# 2022-SS-ZT-1.net
KiCad netlist of a schematic drawn in EasyEDA Pro
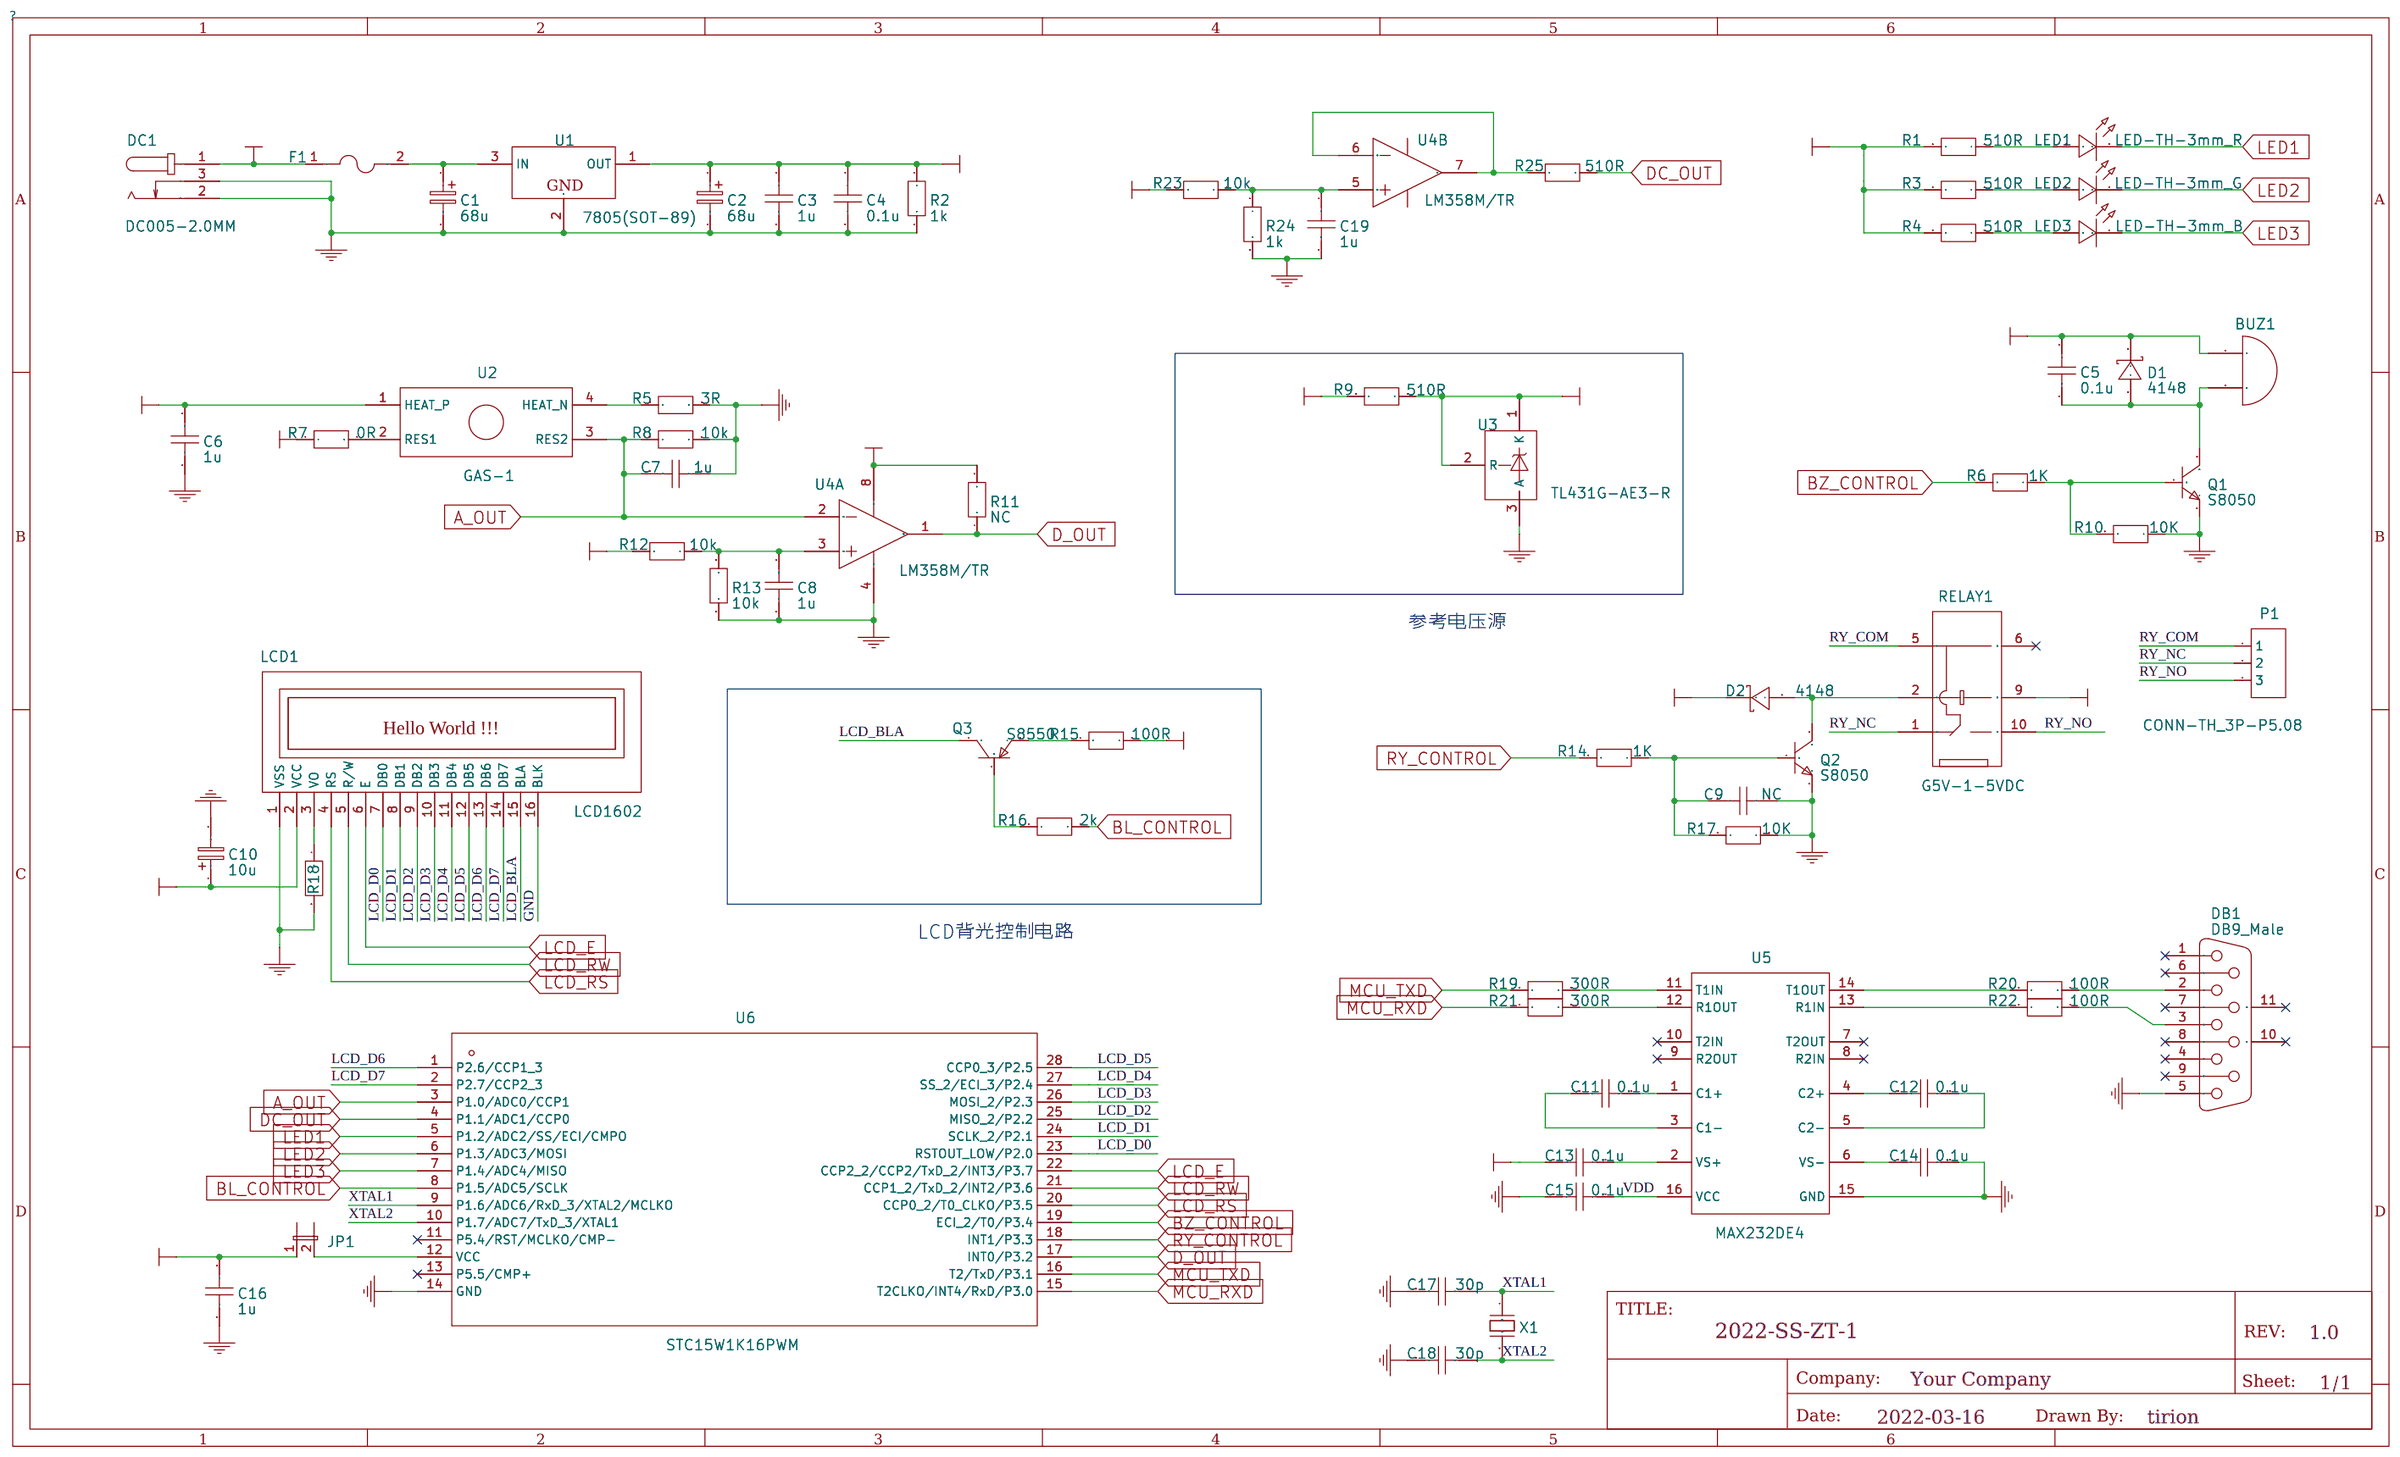
[diagram p0: schematic sheet]

(export (version "E")
  (design (tool "Eeschema 10.0.6"))
  (components
    (comp (ref "BUZ1") (value "BUZ1") (libsource (lib "easyedapro") (part "BUZ1")))
    (comp (ref "C1") (value "68u") (libsource (lib "easyedapro") (part "68u")))
    (comp (ref "C2") (value "68u") (libsource (lib "easyedapro") (part "68u")))
    (comp (ref "C3") (value "1u") (libsource (lib "easyedapro") (part "1u")))
    (comp (ref "C4") (value "0.1u") (libsource (lib "easyedapro") (part "0.1u")))
    (comp (ref "C5") (value "0.1u") (libsource (lib "easyedapro") (part "0.1u")))
    (comp (ref "C6") (value "1u") (libsource (lib "easyedapro") (part "1u")))
    (comp (ref "C7") (value "1u") (libsource (lib "easyedapro") (part "1u")))
    (comp (ref "C8") (value "1u") (libsource (lib "easyedapro") (part "1u")))
    (comp (ref "C9") (value "NC") (libsource (lib "easyedapro") (part "NC")))
    (comp (ref "C10") (value "10u") (libsource (lib "easyedapro") (part "10u")))
    (comp (ref "C11") (value "0.1u") (libsource (lib "easyedapro") (part "0.1u")))
    (comp (ref "C12") (value "0.1u") (libsource (lib "easyedapro") (part "0.1u")))
    (comp (ref "C13") (value "0.1u") (libsource (lib "easyedapro") (part "0.1u")))
    (comp (ref "C14") (value "0.1u") (libsource (lib "easyedapro") (part "0.1u")))
    (comp (ref "C15") (value "0.1u") (libsource (lib "easyedapro") (part "0.1u")))
    (comp (ref "C16") (value "1u") (libsource (lib "easyedapro") (part "1u")))
    (comp (ref "C17") (value "30p") (libsource (lib "easyedapro") (part "30p")))
    (comp (ref "C18") (value "30p") (libsource (lib "easyedapro") (part "30p")))
    (comp (ref "C19") (value "1u") (libsource (lib "easyedapro") (part "1u")))
    (comp (ref "D1")
      (value "4148")
      (fields (field (name "Manufacturer Part") "SS14") (field (name "Manufacturer") "MDD"))
      (libsource (lib "easyedapro") (part "4148"))
    )
    (comp (ref "D2")
      (value "4148")
      (fields (field (name "Manufacturer Part") "SS14") (field (name "Manufacturer") "MDD"))
      (libsource (lib "easyedapro") (part "4148"))
    )
    (comp (ref "DB1")
      (value "DB9_Male")
      (fields (field (name "Manufacturer") "Amphenol"))
      (libsource (lib "easyedapro") (part "DB9_Male"))
    )
    (comp (ref "DC1")
      (value "DC005-2.0MM")
      (fields (field (name "Manufacturer") "SOFNG"))
      (libsource (lib "easyedapro") (part "DC005-2.0MM"))
    )
    (comp (ref "F1") (value "FUSE_F1812_FUSE") (libsource (lib "easyedapro") (part "FUSE_F1812_FUSE")))
    (comp (ref "JP1") (value "JUMPER2") (libsource (lib "easyedapro") (part "JUMPER2")))
    (comp (ref "LCD1")
      (value "LCD1602")
      (fields
        (field (name "Manufacturer Part") "LCM1602K-NSW-BBW")
        (field (name "Manufacturer") "LONTECH(厦门龙特)")
      )
      (libsource (lib "easyedapro") (part "LCD1602"))
    )
    (comp (ref "LED1")
      (value "LED-TH-3mm_R")
      (fields
        (field (name "Manufacturer Part") "204-10SDRD/S530-A3-L")
        (field (name "Manufacturer") "EVERLIGHT(台湾亿光)")
      )
      (libsource (lib "easyedapro") (part "LED-TH-3mm_R"))
    )
    (comp (ref "LED2")
      (value "LED-TH-3mm_G")
      (fields
        (field (name "Manufacturer Part") "204-10SYGD/S530-E3")
        (field (name "Manufacturer") "EVERLIGHT(台湾亿光)")
      )
      (libsource (lib "easyedapro") (part "LED-TH-3mm_G"))
    )
    (comp (ref "LED3")
      (value "LED-TH-3mm_B")
      (fields
        (field (name "Manufacturer Part") "204-10SUBC/S400-A4")
        (field (name "Manufacturer") "EVERLIGHT(台湾亿光)")
      )
      (libsource (lib "easyedapro") (part "LED-TH-3mm_B"))
    )
    (comp (ref "P1") (value "CONN-TH_3P-P5.08") (libsource (lib "easyedapro") (part "CONN-TH_3P-P5.08")))
    (comp (ref "Q1")
      (value "S8050")
      (fields (field (name "Manufacturer") "JSMSEMI"))
      (libsource (lib "easyedapro") (part "S8050"))
    )
    (comp (ref "Q2")
      (value "S8050")
      (fields (field (name "Manufacturer") "JSMSEMI"))
      (libsource (lib "easyedapro") (part "S8050"))
    )
    (comp (ref "Q3")
      (value "S8550")
      (fields
        (field (name "Manufacturer Part") "S8550-H")
        (field (name "Manufacturer") "Yangzhou Yangjie Elec Tech")
      )
      (libsource (lib "easyedapro") (part "S8550"))
    )
    (comp (ref "R1") (value "510R") (libsource (lib "easyedapro") (part "510R")))
    (comp (ref "R2") (value "1k") (libsource (lib "easyedapro") (part "1k")))
    (comp (ref "R3") (value "510R") (libsource (lib "easyedapro") (part "510R")))
    (comp (ref "R4") (value "510R") (libsource (lib "easyedapro") (part "510R")))
    (comp (ref "R5") (value "3R") (libsource (lib "easyedapro") (part "3R")))
    (comp (ref "R6") (value "1K") (libsource (lib "easyedapro") (part "1K")))
    (comp (ref "R7") (value "0R") (libsource (lib "easyedapro") (part "0R")))
    (comp (ref "R8") (value "10k") (libsource (lib "easyedapro") (part "10k")))
    (comp (ref "R9") (value "510R") (libsource (lib "easyedapro") (part "510R")))
    (comp (ref "R10") (value "10K") (libsource (lib "easyedapro") (part "10K")))
    (comp (ref "R11") (value "NC") (libsource (lib "") (part "NC_1")))
    (comp (ref "R12") (value "10k") (libsource (lib "easyedapro") (part "10k")))
    (comp (ref "R13") (value "10k") (libsource (lib "easyedapro") (part "10k")))
    (comp (ref "R14") (value "1K") (libsource (lib "easyedapro") (part "1K")))
    (comp (ref "R15") (value "100R") (libsource (lib "easyedapro") (part "100R")))
    (comp (ref "R16") (value "2k") (libsource (lib "easyedapro") (part "2k")))
    (comp (ref "R17") (value "10K") (libsource (lib "easyedapro") (part "10K")))
    (comp (ref "R18") (value "10k") (libsource (lib "easyedapro") (part "10k")))
    (comp (ref "R19") (value "300R") (libsource (lib "easyedapro") (part "300R")))
    (comp (ref "R20") (value "100R") (libsource (lib "easyedapro") (part "100R")))
    (comp (ref "R21") (value "300R") (libsource (lib "easyedapro") (part "300R")))
    (comp (ref "R22") (value "100R") (libsource (lib "easyedapro") (part "100R")))
    (comp (ref "R23") (value "10k") (libsource (lib "easyedapro") (part "10k")))
    (comp (ref "R24") (value "1k") (libsource (lib "easyedapro") (part "1k")))
    (comp (ref "R25") (value "510R") (libsource (lib "easyedapro") (part "510R")))
    (comp (ref "RELAY1")
      (value "G5V-1-5VDC")
      (fields (field (name "Manufacturer") "OMRON"))
      (libsource (lib "easyedapro") (part "G5V-1-5VDC"))
    )
    (comp (ref "U1")
      (value "7805(SOT-89)")
      (fields (field (name "Manufacturer Part") "CJ78L05") (field (name "Manufacturer") "CJ"))
      (libsource (lib "easyedapro") (part "7805(SOT-89)"))
    )
    (comp (ref "U2") (value "GAS-1") (libsource (lib "easyedapro") (part "GAS-1")))
    (comp (ref "U3")
      (value "TL431G-AE3-R")
      (fields (field (name "Manufacturer") "UTC"))
      (libsource (lib "easyedapro") (part "TL431G-AE3-R"))
    )
    (comp (ref "U4")
      (value "LM358M/TR")
      (fields (field (name "Manufacturer") "HGSEMI"))
      (libsource (lib "easyedapro") (part "LM358M/TR"))
    )
    (comp (ref "U5") (value "MAX232DE4") (libsource (lib "easyedapro") (part "MAX232DE4")))
    (comp (ref "U6")
      (value "STC15W1K16PWM")
      (fields (field (name "Manufacturer") "STC"))
      (libsource (lib "easyedapro") (part "STC15W1K16PWM"))
    )
    (comp (ref "X1")
      (value "12MHZ")
      (fields (field (name "Manufacturer Part") "X49UD12MSD2SC") (field (name "Manufacturer") "LCSC"))
      (libsource (lib "easyedapro") (part "12MHZ"))
    )
  )
  (nets
    (net (code "1") (name "/LCD_BLA") (class "Default")
      (node (ref "LCD1") (pin "15") (pinfunction "BLA_15") (pintype "input"))
      (node (ref "Q3") (pin "3") (pinfunction "C_3") (pintype "input"))
    )
    (net (code "2") (name "/LCD_D0") (class "Default")
      (node (ref "LCD1") (pin "7") (pinfunction "DB0_7") (pintype "input"))
      (node (ref "U6") (pin "23") (pinfunction "RSTOUT_LOW/P2.0_23") (pintype "input"))
    )
    (net (code "3") (name "/LCD_D1") (class "Default")
      (node (ref "LCD1") (pin "8") (pinfunction "DB1_8") (pintype "input"))
      (node (ref "U6") (pin "24") (pinfunction "SCLK_2/P2.1_24") (pintype "input"))
    )
    (net (code "4") (name "/LCD_D2") (class "Default")
      (node (ref "LCD1") (pin "9") (pinfunction "DB2_9") (pintype "input"))
      (node (ref "U6") (pin "25") (pinfunction "MISO_2/P2.2_25") (pintype "input"))
    )
    (net (code "5") (name "/LCD_D3") (class "Default")
      (node (ref "LCD1") (pin "10") (pinfunction "DB3_10") (pintype "input"))
      (node (ref "U6") (pin "26") (pinfunction "MOSI_2/P2.3_26") (pintype "input"))
    )
    (net (code "6") (name "/LCD_D4") (class "Default")
      (node (ref "LCD1") (pin "11") (pinfunction "DB4_11") (pintype "input"))
      (node (ref "U6") (pin "27") (pinfunction "SS_2/ECI_3/P2.4_27") (pintype "input"))
    )
    (net (code "7") (name "/LCD_D5") (class "Default")
      (node (ref "LCD1") (pin "12") (pinfunction "DB5_12") (pintype "input"))
      (node (ref "U6") (pin "28") (pinfunction "CCP0_3/P2.5_28") (pintype "input"))
    )
    (net (code "8") (name "/LCD_D6") (class "Default")
      (node (ref "LCD1") (pin "13") (pinfunction "DB6_13") (pintype "input"))
      (node (ref "U6") (pin "1") (pinfunction "P2.6/CCP1_3_1") (pintype "input"))
    )
    (net (code "9") (name "/LCD_D7") (class "Default")
      (node (ref "LCD1") (pin "14") (pinfunction "DB7_14") (pintype "input"))
      (node (ref "U6") (pin "2") (pinfunction "P2.7/CCP2_3_2") (pintype "input"))
    )
    (net (code "10") (name "/RY_COM") (class "Default")
      (node (ref "P1") (pin "1") (pinfunction "1_1") (pintype "input"))
      (node (ref "RELAY1") (pin "5") (pinfunction "5_5") (pintype "input"))
    )
    (net (code "11") (name "/RY_NC") (class "Default")
      (node (ref "P1") (pin "2") (pinfunction "2_2") (pintype "input"))
      (node (ref "RELAY1") (pin "1") (pinfunction "1_1") (pintype "input"))
    )
    (net (code "12") (name "/RY_NO") (class "Default")
      (node (ref "P1") (pin "3") (pinfunction "3_3") (pintype "input"))
      (node (ref "RELAY1") (pin "10") (pinfunction "10_10") (pintype "input"))
    )
    (net (code "13") (name "/XTAL1") (class "Default")
      (node (ref "C17") (pin "1") (pinfunction "1_1") (pintype "input"))
      (node (ref "U6") (pin "9") (pinfunction "P1.6/ADC6/RxD_3/XTAL2/MCLKO_9") (pintype "input"))
      (node (ref "X1") (pin "1") (pinfunction "OSC1_1") (pintype "input"))
    )
    (net (code "14") (name "/XTAL2") (class "Default")
      (node (ref "C18") (pin "1") (pinfunction "1_1") (pintype "input"))
      (node (ref "U6") (pin "10") (pinfunction "P1.7/ADC7/TxD_3/XTAL1_10") (pintype "input"))
      (node (ref "X1") (pin "2") (pinfunction "OSC2_2") (pintype "input"))
    )
    (net (code "15") (name "A_OUT") (class "Default")
      (node (ref "C7") (pin "2") (pinfunction "2_2") (pintype "input"))
      (node (ref "R8") (pin "1") (pinfunction "1_1") (pintype "input"))
      (node (ref "U2") (pin "3") (pinfunction "RES2_3") (pintype "input"))
      (node (ref "U4") (pin "2") (pinfunction "1IN-_2") (pintype "input"))
      (node (ref "U6") (pin "3") (pinfunction "P1.0/ADC0/CCP1_3") (pintype "input"))
    )
    (net (code "16") (name "BL_CONTROL") (class "Default")
      (node (ref "R16") (pin "2") (pinfunction "2_2") (pintype "input"))
      (node (ref "U6") (pin "8") (pinfunction "P1.5/ADC5/SCLK_8") (pintype "input"))
    )
    (net (code "17") (name "BZ_CONTROL") (class "Default")
      (node (ref "R6") (pin "2") (pinfunction "2_2") (pintype "input"))
      (node (ref "U6") (pin "19") (pinfunction "ECI_2/T0/P3.4_19") (pintype "input"))
    )
    (net (code "18") (name "DC_IN") (class "Default")
      (node (ref "DC1") (pin "1") (pinfunction "1_1") (pintype "input"))
      (node (ref "F1") (pin "1") (pinfunction "1_1") (pintype "input"))
      (node (ref "R23") (pin "2") (pinfunction "2_2") (pintype "input"))
    )
    (net (code "19") (name "DC_OUT") (class "Default")
      (node (ref "R25") (pin "1") (pinfunction "1_1") (pintype "input"))
      (node (ref "U6") (pin "4") (pinfunction "P1.1/ADC1/CCP0_4") (pintype "input"))
    )
    (net (code "20") (name "D_OUT") (class "Default")
      (node (ref "R11") (pin "1") (pinfunction "1_1") (pintype "input"))
      (node (ref "U4") (pin "1") (pinfunction "1OUT_1") (pintype "output"))
      (node (ref "U6") (pin "17") (pinfunction "INT0/P3.2_17") (pintype "input"))
    )
    (net (code "21") (name "GND") (class "Default")
      (node (ref "C1") (pin "2") (pinfunction "2_2") (pintype "input"))
      (node (ref "C10") (pin "2") (pinfunction "2_2") (pintype "input"))
      (node (ref "C14") (pin "2") (pinfunction "2_2") (pintype "input"))
      (node (ref "C15") (pin "1") (pinfunction "1_1") (pintype "input"))
      (node (ref "C16") (pin "1") (pinfunction "1_1") (pintype "input"))
      (node (ref "C17") (pin "2") (pinfunction "2_2") (pintype "input"))
      (node (ref "C18") (pin "2") (pinfunction "2_2") (pintype "input"))
      (node (ref "C19") (pin "2") (pinfunction "2_2") (pintype "input"))
      (node (ref "C2") (pin "2") (pinfunction "2_2") (pintype "input"))
      (node (ref "C3") (pin "2") (pinfunction "2_2") (pintype "input"))
      (node (ref "C4") (pin "2") (pinfunction "2_2") (pintype "input"))
      (node (ref "C6") (pin "1") (pinfunction "1_1") (pintype "input"))
      (node (ref "C7") (pin "1") (pinfunction "1_1") (pintype "input"))
      (node (ref "C8") (pin "2") (pinfunction "2_2") (pintype "input"))
      (node (ref "C9") (pin "2") (pinfunction "2_2") (pintype "input"))
      (node (ref "DB1") (pin "5") (pinfunction "5_5") (pintype "input"))
      (node (ref "DC1") (pin "2") (pinfunction "2_2") (pintype "input"))
      (node (ref "DC1") (pin "3") (pinfunction "3_3") (pintype "input"))
      (node (ref "LCD1") (pin "1") (pinfunction "VSS_1") (pintype "input"))
      (node (ref "LCD1") (pin "16") (pinfunction "BLK_16") (pintype "input"))
      (node (ref "Q1") (pin "2") (pinfunction "E_2") (pintype "input"))
      (node (ref "Q2") (pin "2") (pinfunction "E_2") (pintype "input"))
      (node (ref "R10") (pin "1") (pinfunction "1_1") (pintype "input"))
      (node (ref "R13") (pin "2") (pinfunction "2_2") (pintype "input"))
      (node (ref "R17") (pin "1") (pinfunction "1_1") (pintype "input"))
      (node (ref "R18") (pin "2") (pinfunction "2_2") (pintype "input"))
      (node (ref "R2") (pin "2") (pinfunction "2_2") (pintype "input"))
      (node (ref "R24") (pin "2") (pinfunction "2_2") (pintype "input"))
      (node (ref "R5") (pin "2") (pinfunction "2_2") (pintype "input"))
      (node (ref "R8") (pin "2") (pinfunction "2_2") (pintype "input"))
      (node (ref "U1") (pin "2") (pinfunction "GND_2") (pintype "input"))
      (node (ref "U3") (pin "3") (pinfunction "A_3") (pintype "input"))
      (node (ref "U4") (pin "4") (pinfunction "GND_4") (pintype "input"))
      (node (ref "U5") (pin "15") (pinfunction "GND_15") (pintype "input"))
      (node (ref "U6") (pin "14") (pinfunction "GND_14") (pintype "input"))
    )
    (net (code "22") (name "LCD_E") (class "Default")
      (node (ref "LCD1") (pin "6") (pinfunction "E_6") (pintype "input"))
      (node (ref "U6") (pin "22") (pinfunction "CCP2_2/CCP2/TxD_2/INT3/P3.7_22") (pintype "input"))
    )
    (net (code "23") (name "LCD_RS") (class "Default")
      (node (ref "LCD1") (pin "4") (pinfunction "RS_4") (pintype "input"))
      (node (ref "U6") (pin "20") (pinfunction "CCP0_2/T0_CLKO/P3.5_20") (pintype "input"))
    )
    (net (code "24") (name "LCD_RW") (class "Default")
      (node (ref "LCD1") (pin "5") (pinfunction "R/W_5") (pintype "input"))
      (node (ref "U6") (pin "21") (pinfunction "CCP1_2/TxD_2/INT2/P3.6_21") (pintype "input"))
    )
    (net (code "25") (name "LED1") (class "Default")
      (node (ref "LED1") (pin "2") (pinfunction "2_2") (pintype "input"))
      (node (ref "U6") (pin "5") (pinfunction "P1.2/ADC2/SS/ECI/CMPO_5") (pintype "input"))
    )
    (net (code "26") (name "LED2") (class "Default")
      (node (ref "LED2") (pin "2") (pinfunction "2_2") (pintype "input"))
      (node (ref "U6") (pin "6") (pinfunction "P1.3/ADC3/MOSI_6") (pintype "input"))
    )
    (net (code "27") (name "LED3") (class "Default")
      (node (ref "LED3") (pin "2") (pinfunction "2_2") (pintype "input"))
      (node (ref "U6") (pin "7") (pinfunction "P1.4/ADC4/MISO_7") (pintype "input"))
    )
    (net (code "28") (name "MCU_RXD") (class "Default")
      (node (ref "R21") (pin "1") (pinfunction "1_1") (pintype "input"))
      (node (ref "U6") (pin "15") (pinfunction "T2CLKO/INT4/RxD/P3.0_15") (pintype "input"))
    )
    (net (code "29") (name "MCU_TXD") (class "Default")
      (node (ref "R19") (pin "1") (pinfunction "1_1") (pintype "input"))
      (node (ref "U6") (pin "16") (pinfunction "T2/TxD/P3.1_16") (pintype "input"))
    )
    (net (code "30") (name "Net-(BUZ1-B)") (class "Default")
      (node (ref "BUZ1") (pin "2") (pinfunction "B_2") (pintype "input"))
      (node (ref "C5") (pin "1") (pinfunction "1_1") (pintype "input"))
      (node (ref "D1") (pin "2") (pinfunction "A_2") (pintype "input"))
      (node (ref "Q1") (pin "3") (pinfunction "C_3") (pintype "input"))
    )
    (net (code "31") (name "Net-(D2-A)") (class "Default")
      (node (ref "D2") (pin "2") (pinfunction "A_2") (pintype "input"))
      (node (ref "Q2") (pin "3") (pinfunction "C_3") (pintype "input"))
      (node (ref "RELAY1") (pin "2") (pinfunction "2_2") (pintype "input"))
    )
    (net (code "32") (name "Net-(DB1-Pad2)") (class "Default")
      (node (ref "DB1") (pin "2") (pinfunction "2_2") (pintype "input"))
      (node (ref "R20") (pin "2") (pinfunction "2_2") (pintype "input"))
    )
    (net (code "33") (name "Net-(DB1-Pad3)") (class "Default")
      (node (ref "DB1") (pin "3") (pinfunction "3_3") (pintype "input"))
      (node (ref "R22") (pin "2") (pinfunction "2_2") (pintype "input"))
    )
    (net (code "34") (name "Net-(LCD1-VO)") (class "Default")
      (node (ref "LCD1") (pin "3") (pinfunction "VO_3") (pintype "input"))
      (node (ref "R18") (pin "1") (pinfunction "1_1") (pintype "input"))
    )
    (net (code "35") (name "Net-(LED1-Pad1)") (class "Default")
      (node (ref "LED1") (pin "1") (pinfunction "1_1") (pintype "input"))
      (node (ref "R1") (pin "1") (pinfunction "1_1") (pintype "input"))
    )
    (net (code "36") (name "Net-(LED2-Pad1)") (class "Default")
      (node (ref "LED2") (pin "1") (pinfunction "1_1") (pintype "input"))
      (node (ref "R3") (pin "1") (pinfunction "1_1") (pintype "input"))
    )
    (net (code "37") (name "Net-(LED3-Pad1)") (class "Default")
      (node (ref "LED3") (pin "1") (pinfunction "1_1") (pintype "input"))
      (node (ref "R4") (pin "1") (pinfunction "1_1") (pintype "input"))
    )
    (net (code "38") (name "Net-(Q1-B)") (class "Default")
      (node (ref "Q1") (pin "1") (pinfunction "B_1") (pintype "input"))
      (node (ref "R10") (pin "2") (pinfunction "2_2") (pintype "input"))
      (node (ref "R6") (pin "1") (pinfunction "1_1") (pintype "input"))
    )
    (net (code "39") (name "Net-(Q2-B)") (class "Default")
      (node (ref "C9") (pin "1") (pinfunction "1_1") (pintype "input"))
      (node (ref "Q2") (pin "1") (pinfunction "B_1") (pintype "input"))
      (node (ref "R14") (pin "1") (pinfunction "1_1") (pintype "input"))
      (node (ref "R17") (pin "2") (pinfunction "2_2") (pintype "input"))
    )
    (net (code "40") (name "Net-(Q3-B)") (class "Default")
      (node (ref "Q3") (pin "1") (pinfunction "B_1") (pintype "input"))
      (node (ref "R16") (pin "1") (pinfunction "1_1") (pintype "input"))
    )
    (net (code "41") (name "Net-(Q3-E)") (class "Default")
      (node (ref "Q3") (pin "2") (pinfunction "E_2") (pintype "input"))
      (node (ref "R15") (pin "1") (pinfunction "1_1") (pintype "input"))
    )
    (net (code "42") (name "Net-(U1-IN)") (class "Default")
      (node (ref "C1") (pin "1") (pinfunction "1_1") (pintype "input"))
      (node (ref "F1") (pin "2") (pinfunction "2_2") (pintype "input"))
      (node (ref "U1") (pin "3") (pinfunction "IN_3") (pintype "input"))
    )
    (net (code "43") (name "Net-(U2-HEAT_N)") (class "Default")
      (node (ref "R5") (pin "1") (pinfunction "1_1") (pintype "input"))
      (node (ref "U2") (pin "4") (pinfunction "HEAT_N_4") (pintype "input"))
    )
    (net (code "44") (name "Net-(U2-RES1)") (class "Default")
      (node (ref "R7") (pin "2") (pinfunction "2_2") (pintype "input"))
      (node (ref "U2") (pin "2") (pinfunction "RES1_2") (pintype "input"))
    )
    (net (code "45") (name "Net-(U4A-1IN+)") (class "Default")
      (node (ref "C8") (pin "1") (pinfunction "1_1") (pintype "input"))
      (node (ref "R12") (pin "1") (pinfunction "1_1") (pintype "input"))
      (node (ref "R13") (pin "1") (pinfunction "1_1") (pintype "input"))
      (node (ref "U4") (pin "3") (pinfunction "1IN+_3") (pintype "input"))
    )
    (net (code "46") (name "Net-(U4B-2IN+)") (class "Default")
      (node (ref "C19") (pin "1") (pinfunction "1_1") (pintype "input"))
      (node (ref "R23") (pin "1") (pinfunction "1_1") (pintype "input"))
      (node (ref "R24") (pin "1") (pinfunction "1_1") (pintype "input"))
      (node (ref "U4") (pin "5") (pinfunction "2IN+_5") (pintype "input"))
    )
    (net (code "47") (name "Net-(U4B-2IN-)") (class "Default")
      (node (ref "R25") (pin "2") (pinfunction "2_2") (pintype "input"))
      (node (ref "U4") (pin "6") (pinfunction "2IN-_6") (pintype "input"))
      (node (ref "U4") (pin "7") (pinfunction "2OUT_7") (pintype "output"))
    )
    (net (code "48") (name "Net-(U5-C1+)") (class "Default")
      (node (ref "C11") (pin "2") (pinfunction "2_2") (pintype "input"))
      (node (ref "U5") (pin "1") (pinfunction "C1+_1") (pintype "input"))
    )
    (net (code "49") (name "Net-(U5-C1-)") (class "Default")
      (node (ref "C11") (pin "1") (pinfunction "1_1") (pintype "input"))
      (node (ref "U5") (pin "3") (pinfunction "C1-_3") (pintype "input"))
    )
    (net (code "50") (name "Net-(U5-C2+)") (class "Default")
      (node (ref "C12") (pin "1") (pinfunction "1_1") (pintype "input"))
      (node (ref "U5") (pin "4") (pinfunction "C2+_4") (pintype "input"))
    )
    (net (code "51") (name "Net-(U5-C2-)") (class "Default")
      (node (ref "C12") (pin "2") (pinfunction "2_2") (pintype "input"))
      (node (ref "U5") (pin "5") (pinfunction "C2-_5") (pintype "input"))
    )
    (net (code "52") (name "Net-(U5-R1IN)") (class "Default")
      (node (ref "R22") (pin "1") (pinfunction "1_1") (pintype "input"))
      (node (ref "U5") (pin "13") (pinfunction "R1IN_13") (pintype "input"))
    )
    (net (code "53") (name "Net-(U5-R1OUT)") (class "Default")
      (node (ref "R21") (pin "2") (pinfunction "2_2") (pintype "input"))
      (node (ref "U5") (pin "12") (pinfunction "R1OUT_12") (pintype "output"))
    )
    (net (code "54") (name "Net-(U5-T1IN)") (class "Default")
      (node (ref "R19") (pin "2") (pinfunction "2_2") (pintype "input"))
      (node (ref "U5") (pin "11") (pinfunction "T1IN_11") (pintype "input"))
    )
    (net (code "55") (name "Net-(U5-T1OUT)") (class "Default")
      (node (ref "R20") (pin "1") (pinfunction "1_1") (pintype "input"))
      (node (ref "U5") (pin "14") (pinfunction "T1OUT_14") (pintype "output"))
    )
    (net (code "56") (name "Net-(U5-VS+)") (class "Default")
      (node (ref "C13") (pin "2") (pinfunction "2_2") (pintype "input"))
      (node (ref "U5") (pin "2") (pinfunction "VS+_2") (pintype "input"))
    )
    (net (code "57") (name "Net-(U5-VS-)") (class "Default")
      (node (ref "C14") (pin "1") (pinfunction "1_1") (pintype "input"))
      (node (ref "U5") (pin "6") (pinfunction "VS-_6") (pintype "input"))
    )
    (net (code "58") (name "Net-(U6-VCC)") (class "Default")
      (node (ref "JP1") (pin "2") (pinfunction "2_2") (pintype "input"))
      (node (ref "U6") (pin "12") (pinfunction "VCC_12") (pintype "input"))
    )
    (net (code "59") (name "RY_CONTROL") (class "Default")
      (node (ref "R14") (pin "2") (pinfunction "2_2") (pintype "input"))
      (node (ref "U6") (pin "18") (pinfunction "INT1/P3.3_18") (pintype "input"))
    )
    (net (code "60") (name "VDD") (class "Default")
      (node (ref "BUZ1") (pin "1") (pinfunction "A_1") (pintype "input"))
      (node (ref "C10") (pin "1") (pinfunction "1_1") (pintype "input"))
      (node (ref "C13") (pin "1") (pinfunction "1_1") (pintype "input"))
      (node (ref "C15") (pin "2") (pinfunction "2_2") (pintype "input"))
      (node (ref "C16") (pin "2") (pinfunction "2_2") (pintype "input"))
      (node (ref "C2") (pin "1") (pinfunction "1_1") (pintype "input"))
      (node (ref "C3") (pin "1") (pinfunction "1_1") (pintype "input"))
      (node (ref "C4") (pin "1") (pinfunction "1_1") (pintype "input"))
      (node (ref "C5") (pin "2") (pinfunction "2_2") (pintype "input"))
      (node (ref "C6") (pin "2") (pinfunction "2_2") (pintype "input"))
      (node (ref "D1") (pin "1") (pinfunction "K_1") (pintype "input"))
      (node (ref "D2") (pin "1") (pinfunction "K_1") (pintype "input"))
      (node (ref "JP1") (pin "1") (pinfunction "1_1") (pintype "input"))
      (node (ref "LCD1") (pin "2") (pinfunction "VCC_2") (pintype "input"))
      (node (ref "R1") (pin "2") (pinfunction "2_2") (pintype "input"))
      (node (ref "R11") (pin "2") (pinfunction "2_2") (pintype "input"))
      (node (ref "R15") (pin "2") (pinfunction "2_2") (pintype "input"))
      (node (ref "R2") (pin "1") (pinfunction "1_1") (pintype "input"))
      (node (ref "R3") (pin "2") (pinfunction "2_2") (pintype "input"))
      (node (ref "R4") (pin "2") (pinfunction "2_2") (pintype "input"))
      (node (ref "R9") (pin "2") (pinfunction "2_2") (pintype "input"))
      (node (ref "RELAY1") (pin "9") (pinfunction "9_9") (pintype "input"))
      (node (ref "U1") (pin "1") (pinfunction "OUT_1") (pintype "input"))
      (node (ref "U2") (pin "1") (pinfunction "HEAT_P_1") (pintype "input"))
      (node (ref "U4") (pin "8") (pinfunction "VCC_8") (pintype "input"))
      (node (ref "U5") (pin "16") (pinfunction "VCC_16") (pintype "input"))
    )
    (net (code "61") (name "VREF") (class "Default")
      (node (ref "R12") (pin "2") (pinfunction "2_2") (pintype "input"))
      (node (ref "R7") (pin "1") (pinfunction "1_1") (pintype "input"))
      (node (ref "R9") (pin "1") (pinfunction "1_1") (pintype "input"))
      (node (ref "U3") (pin "1") (pinfunction "K_1") (pintype "input"))
      (node (ref "U3") (pin "2") (pinfunction "R_2") (pintype "input"))
    )
    (net (code "62") (name "unconnected-(DB1-MH1-Pad10)") (class "Default")
      (node (ref "DB1") (pin "10") (pinfunction "MH1_10") (pintype "input+no_connect"))
    )
    (net (code "63") (name "unconnected-(DB1-MH2-Pad11)") (class "Default")
      (node (ref "DB1") (pin "11") (pinfunction "MH2_11") (pintype "input+no_connect"))
    )
    (net (code "64") (name "unconnected-(DB1-Pad1)") (class "Default")
      (node (ref "DB1") (pin "1") (pinfunction "1_1") (pintype "input+no_connect"))
    )
    (net (code "65") (name "unconnected-(DB1-Pad4)") (class "Default")
      (node (ref "DB1") (pin "4") (pinfunction "4_4") (pintype "input+no_connect"))
    )
    (net (code "66") (name "unconnected-(DB1-Pad6)") (class "Default")
      (node (ref "DB1") (pin "6") (pinfunction "6_6") (pintype "input+no_connect"))
    )
    (net (code "67") (name "unconnected-(DB1-Pad7)") (class "Default")
      (node (ref "DB1") (pin "7") (pinfunction "7_7") (pintype "input+no_connect"))
    )
    (net (code "68") (name "unconnected-(DB1-Pad8)") (class "Default")
      (node (ref "DB1") (pin "8") (pinfunction "8_8") (pintype "input+no_connect"))
    )
    (net (code "69") (name "unconnected-(DB1-Pad9)") (class "Default")
      (node (ref "DB1") (pin "9") (pinfunction "9_9") (pintype "input+no_connect"))
    )
    (net (code "70") (name "unconnected-(RELAY1-Pad6)") (class "Default")
      (node (ref "RELAY1") (pin "6") (pinfunction "6_6") (pintype "input+no_connect"))
    )
    (net (code "71") (name "unconnected-(U5-R2IN-Pad8)") (class "Default")
      (node (ref "U5") (pin "8") (pinfunction "R2IN_8") (pintype "input+no_connect"))
    )
    (net (code "72") (name "unconnected-(U5-R2OUT-Pad9)") (class "Default")
      (node (ref "U5") (pin "9") (pinfunction "R2OUT_9") (pintype "output+no_connect"))
    )
    (net (code "73") (name "unconnected-(U5-T2IN-Pad10)") (class "Default")
      (node (ref "U5") (pin "10") (pinfunction "T2IN_10") (pintype "input+no_connect"))
    )
    (net (code "74") (name "unconnected-(U5-T2OUT-Pad7)") (class "Default")
      (node (ref "U5") (pin "7") (pinfunction "T2OUT_7") (pintype "output+no_connect"))
    )
    (net (code "75") (name "unconnected-(U6-P5.4{slash}RST{slash}MCLKO{slash}CMP--Pad11)") (class "Default")
      (node (ref "U6") (pin "11") (pinfunction "P5.4/RST/MCLKO/CMP-_11") (pintype "input+no_connect"))
    )
    (net (code "76") (name "unconnected-(U6-P5.5{slash}CMP+-Pad13)") (class "Default")
      (node (ref "U6") (pin "13") (pinfunction "P5.5/CMP+_13") (pintype "input+no_connect"))
    )
  )
)
